# SX1308.net
KiCad netlist of a schematic drawn in Altium Designer
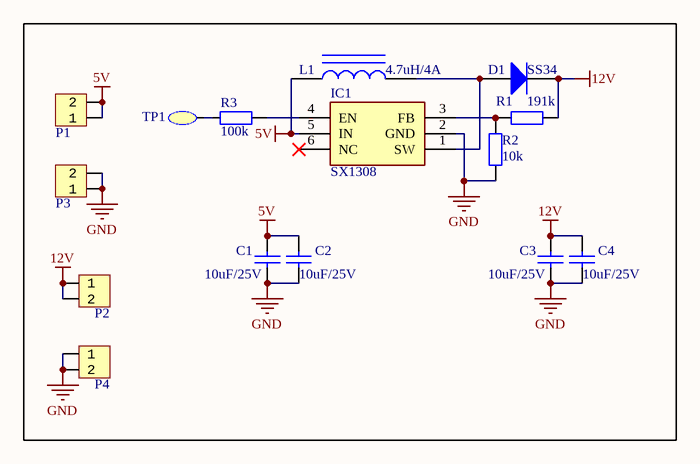
[diagram p0: SX1308.SchDoc]

(export (version "E")
  (design (tool "Eeschema 10.0.6"))
  (components
    (comp (ref "C1")
      (value "10uF/25V")
      (footprint "CAP-0603")
      (description "X7R")
      (libsource (lib "Power_Lib_Altium") (part "CAP"))
    )
    (comp (ref "C2")
      (value "10uF/25V")
      (footprint "CAP-0603")
      (description "X7R")
      (libsource (lib "Power_Lib_Altium") (part "CAP"))
    )
    (comp (ref "C3")
      (value "10uF/25V")
      (footprint "CAP-0603")
      (description "X7R")
      (libsource (lib "Power_Lib_Altium") (part "CAP"))
    )
    (comp (ref "C4")
      (value "10uF/25V")
      (footprint "CAP-0603")
      (description "X7R")
      (libsource (lib "Power_Lib_Altium") (part "CAP"))
    )
    (comp (ref "D1")
      (value "SS34")
      (footprint "DO-214AC/SMA")
      (description "二极管")
      (libsource (lib "Power_Lib_Altium") (part "DIODE"))
    )
    (comp (ref "IC1")
      (value "SX1308")
      (footprint "SOT-23-6")
      (description "集成升压芯片")
      (libsource (lib "Power_Lib_Altium") (part "SX1308"))
    )
    (comp (ref "L1")
      (value "4.7uH/4A")
      (footprint "SMD_7.3x7.3x4.2mm")
      (description "电感")
      (libsource (lib "Power_Lib_Altium") (part "INDUCTOR"))
    )
    (comp (ref "P1")
      (value "HDR1x2_2.54")
      (footprint "HDR1X2_2.54_180")
      (description "Header")
      (libsource (lib "") (part "HDR1x2_2.54_1"))
    )
    (comp (ref "P2")
      (value "HDR1x2_2.54")
      (footprint "HDR1X2_2.54_180")
      (description "Header")
      (libsource (lib "Power_Lib_Altium") (part "HDR1x2_2.54"))
    )
    (comp (ref "P3")
      (value "HDR1x2_2.54")
      (footprint "HDR1X2_2.54_180")
      (description "Header")
      (libsource (lib "") (part "HDR1x2_2.54_1"))
    )
    (comp (ref "P4")
      (value "HDR1x2_2.54")
      (footprint "HDR1X2_2.54_180")
      (description "Header")
      (libsource (lib "Power_Lib_Altium") (part "HDR1x2_2.54"))
    )
    (comp (ref "R1")
      (value "191k")
      (footprint "R-0603")
      (description "贴片电阻")
      (libsource (lib "Power_Lib_Altium") (part "RES"))
    )
    (comp (ref "R2")
      (value "10k")
      (footprint "R-0603")
      (description "贴片电阻")
      (libsource (lib "") (part "RES_1"))
    )
    (comp (ref "R3")
      (value "100k")
      (footprint "R-0603")
      (description "贴片电阻")
      (libsource (lib "Power_Lib_Altium") (part "RES"))
    )
    (comp (ref "TP1")
      (value "TestPoint")
      (footprint "TestPoint")
      (description "测试点")
      (libsource (lib "Power_Lib_Altium") (part "TestPoint"))
    )
  )
  (nets
    (net (code "1") (name "5V") (class "Default")
      (node (ref "C1") (pin "2") (pinfunction "2_2") (pintype "passive"))
      (node (ref "C2") (pin "2") (pinfunction "2_2") (pintype "passive"))
      (node (ref "IC1") (pin "5") (pinfunction "IN_5") (pintype "passive"))
      (node (ref "L1") (pin "1") (pinfunction "1_1") (pintype "passive"))
      (node (ref "P1") (pin "1") (pinfunction "1_1") (pintype "passive"))
      (node (ref "P1") (pin "2") (pinfunction "2_2") (pintype "passive"))
    )
    (net (code "2") (name "12V") (class "Default")
      (node (ref "C3") (pin "2") (pinfunction "2_2") (pintype "passive"))
      (node (ref "C4") (pin "2") (pinfunction "2_2") (pintype "passive"))
      (node (ref "D1") (pin "2") (pinfunction "K_2") (pintype "passive"))
      (node (ref "P2") (pin "1") (pinfunction "1_1") (pintype "passive"))
      (node (ref "P2") (pin "2") (pinfunction "2_2") (pintype "passive"))
      (node (ref "R1") (pin "2") (pinfunction "2_2") (pintype "passive"))
    )
    (net (code "3") (name "GND") (class "Default")
      (node (ref "C1") (pin "1") (pinfunction "1_1") (pintype "passive"))
      (node (ref "C2") (pin "1") (pinfunction "1_1") (pintype "passive"))
      (node (ref "C3") (pin "1") (pinfunction "1_1") (pintype "passive"))
      (node (ref "C4") (pin "1") (pinfunction "1_1") (pintype "passive"))
      (node (ref "IC1") (pin "2") (pinfunction "GND_2") (pintype "passive"))
      (node (ref "P3") (pin "1") (pinfunction "1_1") (pintype "passive"))
      (node (ref "P3") (pin "2") (pinfunction "2_2") (pintype "passive"))
      (node (ref "P4") (pin "1") (pinfunction "1_1") (pintype "passive"))
      (node (ref "P4") (pin "2") (pinfunction "2_2") (pintype "passive"))
      (node (ref "R2") (pin "1") (pinfunction "1_1") (pintype "passive"))
    )
    (net (code "4") (name "Net-(D1-A)") (class "Default")
      (node (ref "D1") (pin "1") (pinfunction "A_1") (pintype "passive"))
      (node (ref "IC1") (pin "1") (pinfunction "SW_1") (pintype "passive"))
      (node (ref "L1") (pin "2") (pinfunction "2_2") (pintype "passive"))
    )
    (net (code "5") (name "Net-(IC1-EN)") (class "Default")
      (node (ref "IC1") (pin "4") (pinfunction "EN_4") (pintype "passive"))
      (node (ref "R3") (pin "2") (pinfunction "2_2") (pintype "passive"))
    )
    (net (code "6") (name "Net-(IC1-FB)") (class "Default")
      (node (ref "IC1") (pin "3") (pinfunction "FB_3") (pintype "passive"))
      (node (ref "R1") (pin "1") (pinfunction "1_1") (pintype "passive"))
      (node (ref "R2") (pin "2") (pinfunction "2_2") (pintype "passive"))
    )
    (net (code "7") (name "Net-(R3-Pad1)") (class "Default")
      (node (ref "R3") (pin "1") (pinfunction "1_1") (pintype "passive"))
      (node (ref "TP1") (pin "1") (pinfunction "1_1") (pintype "passive"))
    )
    (net (code "8") (name "unconnected-(IC1-NC-Pad6)") (class "Default")
      (node (ref "IC1") (pin "6") (pinfunction "NC_6") (pintype "passive+no_connect"))
    )
  )
)
